# ltk-hall_main_vr.net
KiCad netlist of a schematic drawn in Altium Designer
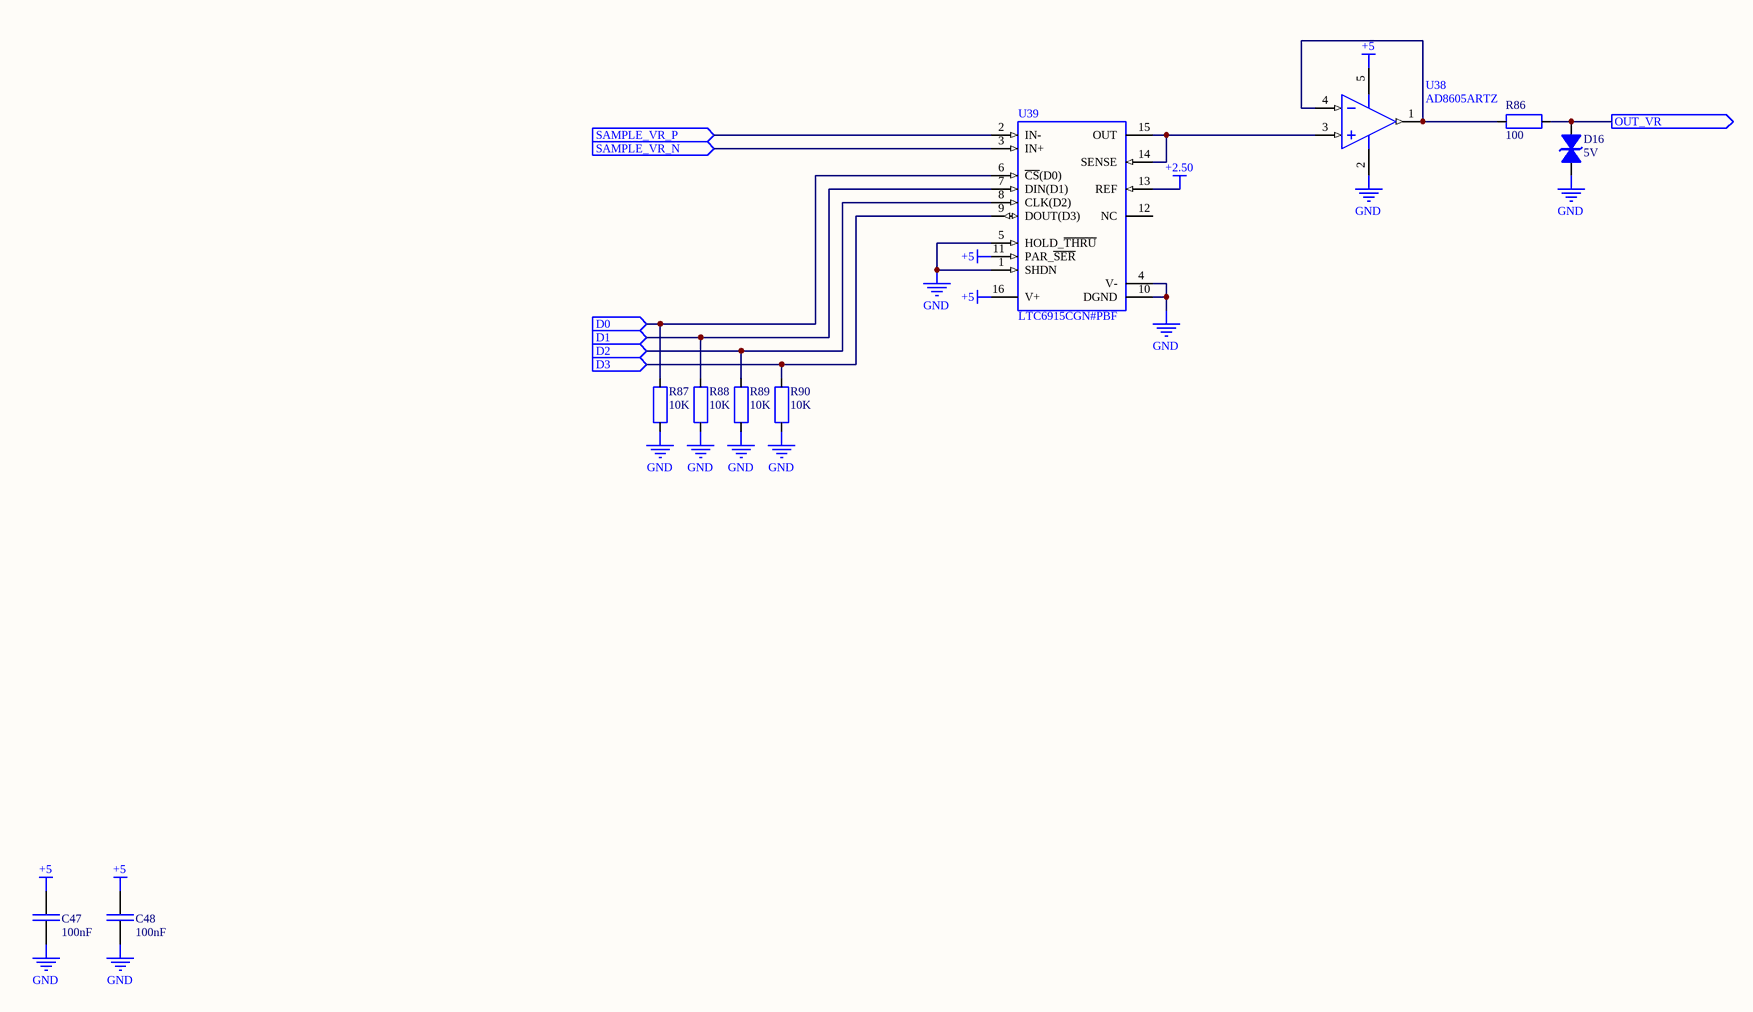
[diagram p0: ltk-hall_main_vr.SchDoc]

(export (version "E")
  (design (tool "Eeschema 10.0.6"))
  (components
    (comp (ref "C47")
      (value "100nF")
      (footprint "CAP 0603_1608")
      (description "CAP SMD MLCC 100nF 25V 0603 X7R")
      (fields (field (name "PART NUMBER") "02841f84-ac15-41b5-9e17-915f8f067828"))
      (libsource (lib "frmdblib") (part "GENERIC_C"))
    )
    (comp (ref "C48")
      (value "100nF")
      (footprint "CAP 0603_1608")
      (description "CAP SMD MLCC 100nF 25V 0603 X7R")
      (fields (field (name "PART NUMBER") "02841f84-ac15-41b5-9e17-915f8f067828"))
      (libsource (lib "frmdblib") (part "GENERIC_C"))
    )
    (comp (ref "D16")
      (value "5V")
      (footprint "SOD523F")
      (description "DIODE SMD TVS 5V BIDIRECTIONAL SOD-523")
      (fields (field (name "PART NUMBER") "daa58212-38e2-4326-a156-8e48058c46f1"))
      (libsource (lib "frmdblib") (part "GENERIC_D_TVS_BI"))
    )
    (comp (ref "R86")
      (value "100")
      (footprint "RES 0603_1608")
      (description "RES SMD 100 OHM 1% 1/10W 0603")
      (fields (field (name "PART NUMBER") "0a6c4b74-f837-4563-b154-6e196d753525"))
      (libsource (lib "frmdblib") (part "GENERIC_R"))
    )
    (comp (ref "R87")
      (value "10K")
      (footprint "RES 0603_1608")
      (description "RES SMD 10K OHM 1% 1/10W 0603")
      (fields (field (name "PART NUMBER") "93242766-ba1d-462d-b58f-ce1dfc4129c8"))
      (libsource (lib "frmdblib") (part "GENERIC_R"))
    )
    (comp (ref "R88")
      (value "10K")
      (footprint "RES 0603_1608")
      (description "RES SMD 10K OHM 1% 1/10W 0603")
      (fields (field (name "PART NUMBER") "93242766-ba1d-462d-b58f-ce1dfc4129c8"))
      (libsource (lib "frmdblib") (part "GENERIC_R"))
    )
    (comp (ref "R89")
      (value "10K")
      (footprint "RES 0603_1608")
      (description "RES SMD 10K OHM 1% 1/10W 0603")
      (fields (field (name "PART NUMBER") "93242766-ba1d-462d-b58f-ce1dfc4129c8"))
      (libsource (lib "frmdblib") (part "GENERIC_R"))
    )
    (comp (ref "R90")
      (value "10K")
      (footprint "RES 0603_1608")
      (description "RES SMD 10K OHM 1% 1/10W 0603")
      (fields (field (name "PART NUMBER") "93242766-ba1d-462d-b58f-ce1dfc4129c8"))
      (libsource (lib "frmdblib") (part "GENERIC_R"))
    )
    (comp (ref "U38")
      (value "AD8605ARTZ")
      (footprint "A3DDA0BC-073E-4B18-9613-F713A7EC1E27")
      (description "IC OPAMP 65uV 1pA RRIO 5V 80mA SOT-23-5")
      (fields (field (name "PART NUMBER") "5610e9ea-bca8-49b2-8e5f-11409231f6a4"))
      (libsource (lib "frmdblib") (part "8096D751-9DCE-401B-B65E-AAEE0733EA70"))
    )
    (comp (ref "U39")
      (value "LTC6915CGN#PBF")
      (footprint "517EE8A2-9FD8-4174-996D-BDBF76CA3EEB")
      (description "IC PGA G0-4094 SPI-PARALLEL 5V RRIO SSOP-16")
      (fields (field (name "PART NUMBER") "59fe82cd-fd18-4813-9f52-e2e78a460aff"))
      (libsource (lib "frmdblib") (part "092C41BF-C4B2-4D13-B4E9-531E546592A0"))
    )
  )
  (nets
    (net (code "1") (name "+2.50") (class "Default")
      (node (ref "U39") (pin "13") (pinfunction "REF_13") (pintype "input"))
    )
    (net (code "2") (name "+5") (class "Default")
      (node (ref "C47") (pin "1") (pintype "passive"))
      (node (ref "C48") (pin "1") (pintype "passive"))
      (node (ref "U38") (pin "5") (pinfunction "+V_5") (pintype "power_in"))
      (node (ref "U39") (pin "11") (pinfunction "PAR_~{SER}_11") (pintype "input"))
      (node (ref "U39") (pin "16") (pinfunction "V+_16") (pintype "power_in"))
    )
    (net (code "3") (name "/D0") (class "Default")
      (node (ref "R87") (pin "2") (pintype "passive"))
      (node (ref "U39") (pin "6") (pinfunction "~{CS}(D0)_6") (pintype "input"))
    )
    (net (code "4") (name "/D1") (class "Default")
      (node (ref "R88") (pin "2") (pintype "passive"))
      (node (ref "U39") (pin "7") (pinfunction "DIN(D1)_7") (pintype "input"))
    )
    (net (code "5") (name "/D2") (class "Default")
      (node (ref "R89") (pin "2") (pintype "passive"))
      (node (ref "U39") (pin "8") (pinfunction "CLK(D2)_8") (pintype "input"))
    )
    (net (code "6") (name "/D3") (class "Default")
      (node (ref "R90") (pin "2") (pintype "passive"))
      (node (ref "U39") (pin "9") (pinfunction "DOUT(D3)_9") (pintype "bidirectional"))
    )
    (net (code "7") (name "/OUT_VR") (class "Default")
      (node (ref "D16") (pin "1") (pintype "passive"))
      (node (ref "R86") (pin "2") (pintype "passive"))
    )
    (net (code "8") (name "/SAMPLE_VR_N") (class "Default")
      (node (ref "U39") (pin "3") (pinfunction "IN+_3") (pintype "input"))
    )
    (net (code "9") (name "/SAMPLE_VR_P") (class "Default")
      (node (ref "U39") (pin "2") (pinfunction "IN-_2") (pintype "input"))
    )
    (net (code "10") (name "GND") (class "Default")
      (node (ref "C47") (pin "2") (pintype "passive"))
      (node (ref "C48") (pin "2") (pintype "passive"))
      (node (ref "D16") (pin "2") (pintype "passive"))
      (node (ref "R87") (pin "1") (pintype "passive"))
      (node (ref "R88") (pin "1") (pintype "passive"))
      (node (ref "R89") (pin "1") (pintype "passive"))
      (node (ref "R90") (pin "1") (pintype "passive"))
      (node (ref "U38") (pin "2") (pinfunction "-V_2") (pintype "power_in"))
      (node (ref "U39") (pin "1") (pinfunction "SHDN_1") (pintype "input"))
      (node (ref "U39") (pin "10") (pinfunction "DGND_10") (pintype "power_in"))
      (node (ref "U39") (pin "4") (pinfunction "V-_4") (pintype "power_in"))
      (node (ref "U39") (pin "5") (pinfunction "HOLD_~{THRU}_5") (pintype "input"))
    )
    (net (code "11") (name "Net-(U38-+IN)") (class "Default")
      (node (ref "U38") (pin "3") (pinfunction "+IN_3") (pintype "input"))
      (node (ref "U39") (pin "14") (pinfunction "SENSE_14") (pintype "input"))
      (node (ref "U39") (pin "15") (pinfunction "OUT_15") (pintype "tri_state"))
    )
    (net (code "12") (name "Net-(U38--IN)") (class "Default")
      (node (ref "R86") (pin "1") (pintype "passive"))
      (node (ref "U38") (pin "1") (pinfunction "OUT_1") (pintype "output"))
      (node (ref "U38") (pin "4") (pinfunction "-IN_4") (pintype "input"))
    )
    (net (code "13") (name "unconnected-(U39-NC-Pad12)") (class "Default")
      (node (ref "U39") (pin "12") (pinfunction "NC_12") (pintype "passive"))
    )
  )
)
